# RocketFlightComputer.net
KiCad netlist of a schematic drawn in EAGLE
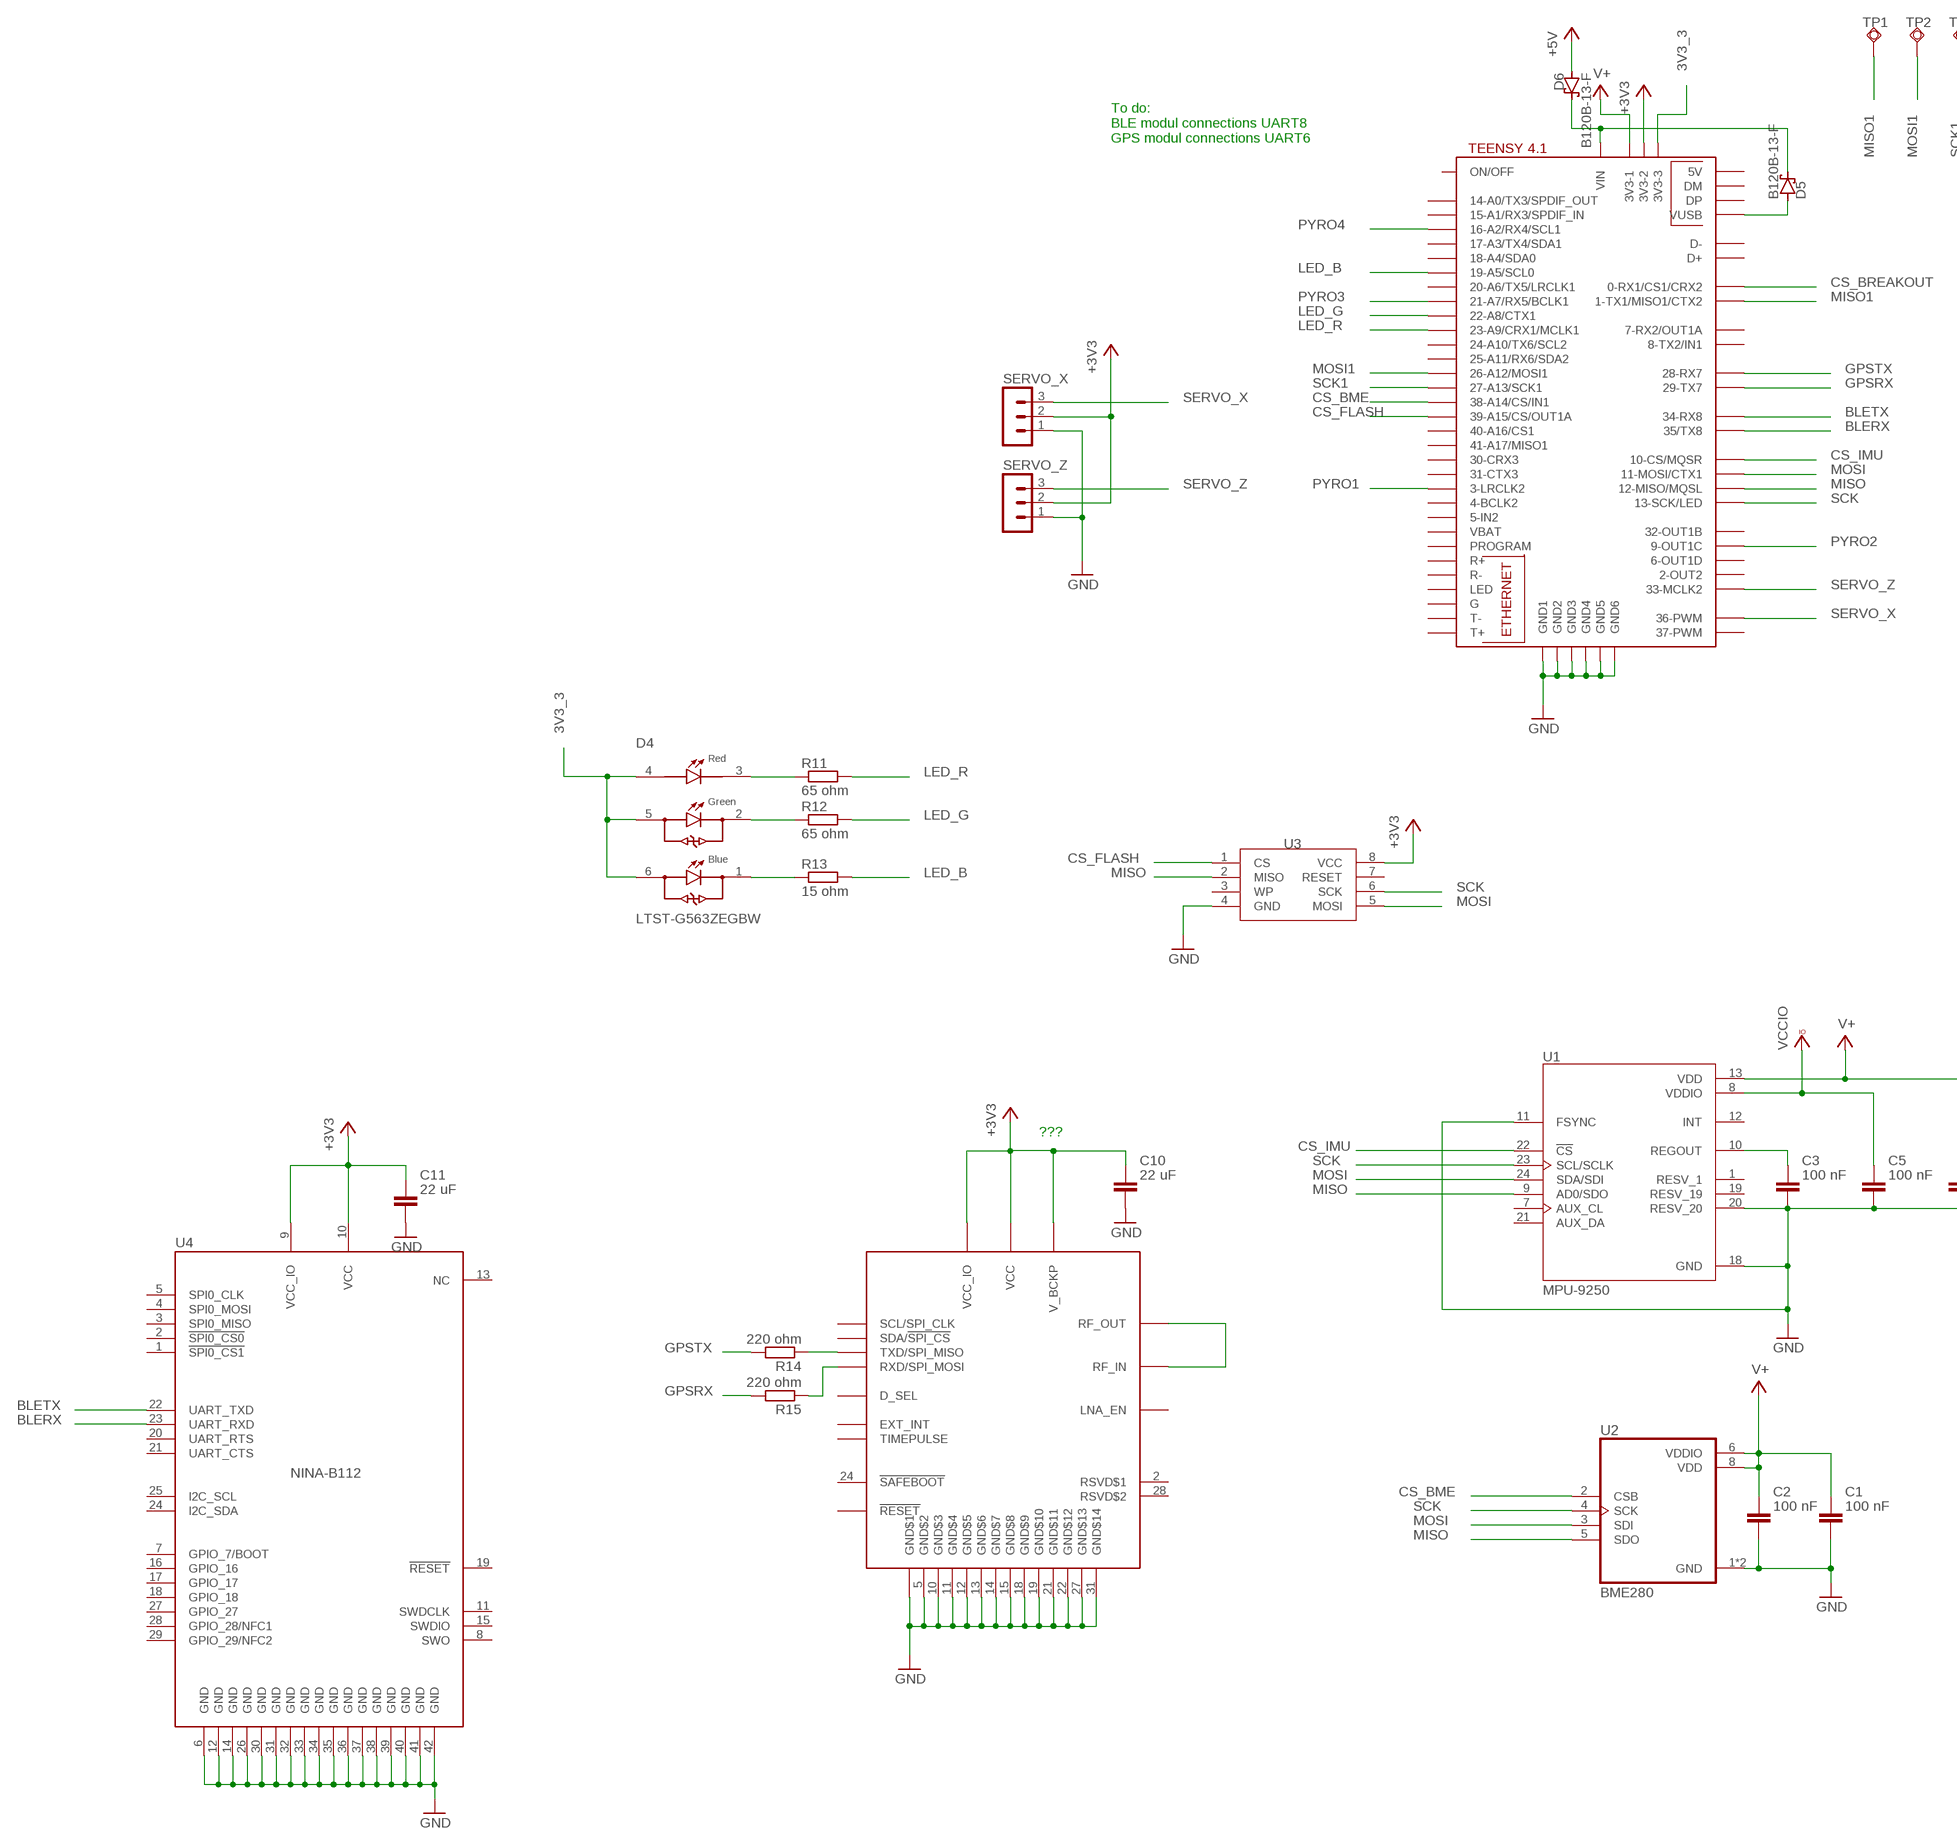
[diagram p0: schematic, sheet 1, part 1 of 2]
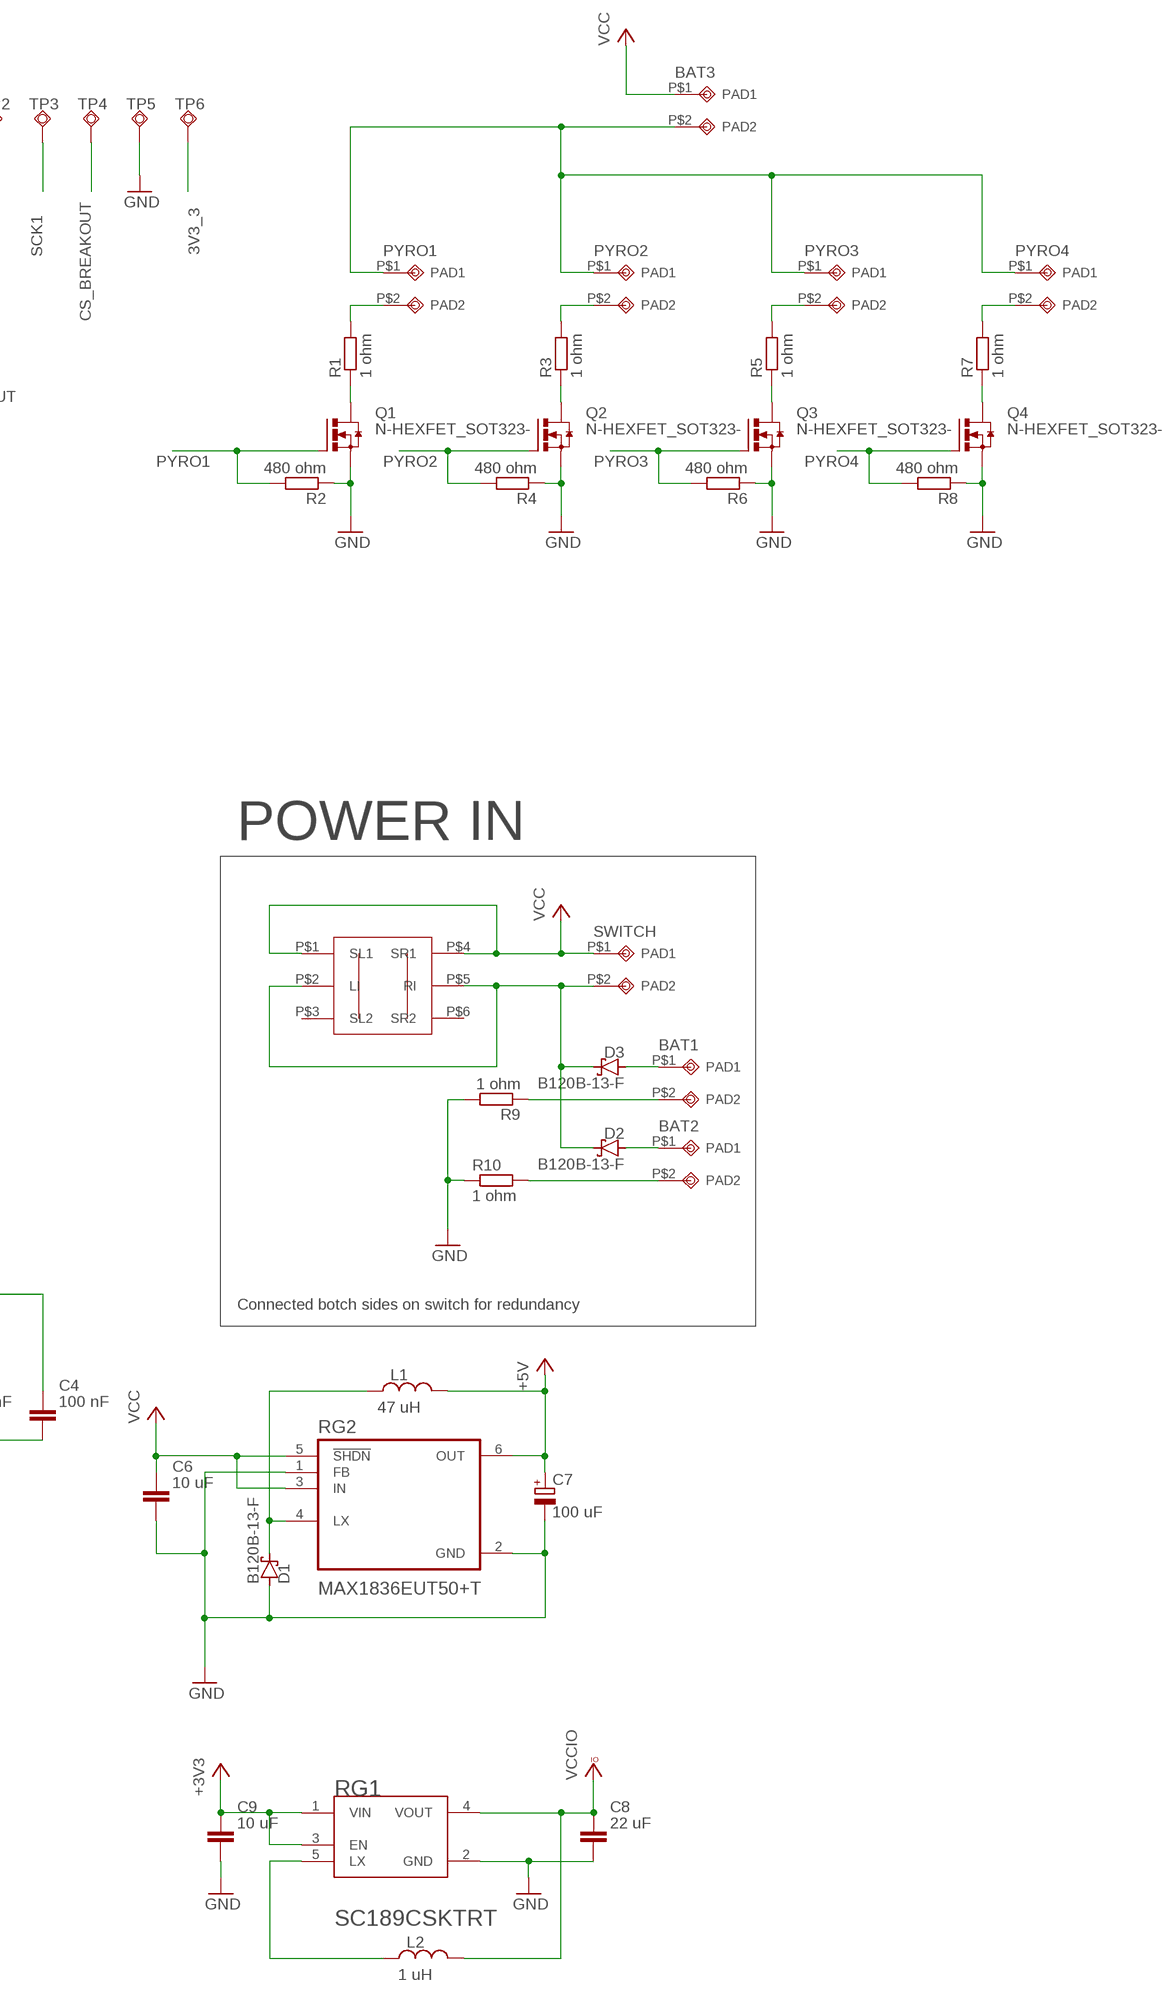
[diagram p1: schematic, sheet 1, part 2 of 2]

(export (version "E")
  (design (tool "Eeschema 10.0.6"))
  (components
    (comp (ref "BAT1")
      (value "2PINPAD")
      (footprint "eagle-import:2PINPAD")
      (libsource (lib "eagle-import") (part "2PINPAD"))
    )
    (comp (ref "BAT2")
      (value "2PINPAD")
      (footprint "eagle-import:2PINPAD")
      (libsource (lib "eagle-import") (part "2PINPAD"))
    )
    (comp (ref "BAT3")
      (value "2PINPAD")
      (footprint "eagle-import:2PINPAD")
      (libsource (lib "eagle-import") (part "2PINPAD"))
    )
    (comp (ref "C1")
      (value "100 nF")
      (footprint "eagle-import:CAPC3216X135")
      (libsource (lib "eagle-import") (part "CCHIP-1206(3216-METRIC)_"))
    )
    (comp (ref "C2")
      (value "100 nF")
      (footprint "eagle-import:CAPC3216X135")
      (libsource (lib "eagle-import") (part "CCHIP-1206(3216-METRIC)_"))
    )
    (comp (ref "C3")
      (value "100 nF")
      (footprint "eagle-import:CAPC3216X135")
      (libsource (lib "eagle-import") (part "CCHIP-1206(3216-METRIC)_"))
    )
    (comp (ref "C4")
      (value "100 nF")
      (footprint "eagle-import:CAPC3216X135")
      (libsource (lib "eagle-import") (part "CCHIP-1206(3216-METRIC)_"))
    )
    (comp (ref "C5")
      (value "100 nF")
      (footprint "eagle-import:CAPC3216X135")
      (libsource (lib "eagle-import") (part "CCHIP-1206(3216-METRIC)_"))
    )
    (comp (ref "C6")
      (value "10 uF")
      (footprint "eagle-import:CAPC3216X135")
      (libsource (lib "eagle-import") (part "CCHIP-1206(3216-METRIC)_"))
    )
    (comp (ref "C7")
      (value "100 uF")
      (footprint "eagle-import:B_3528-21W")
      (libsource (lib "eagle-import") (part "CPOL-EUB/3528-21W"))
    )
    (comp (ref "C8")
      (value "22 uF")
      (footprint "eagle-import:CAPC3216X135")
      (libsource (lib "eagle-import") (part "CCHIP-1206(3216-METRIC)_"))
    )
    (comp (ref "C9")
      (value "10 uF")
      (footprint "eagle-import:CAPC3216X135")
      (libsource (lib "eagle-import") (part "CCHIP-1206(3216-METRIC)_"))
    )
    (comp (ref "C10")
      (value "22 uF")
      (footprint "eagle-import:CAPC3216X135")
      (libsource (lib "eagle-import") (part "CCHIP-1206(3216-METRIC)_"))
    )
    (comp (ref "C11")
      (value "22 uF")
      (footprint "eagle-import:CAPC3216X135")
      (libsource (lib "eagle-import") (part "CCHIP-1206(3216-METRIC)_"))
    )
    (comp (ref "D1")
      (value "B120B-13-F")
      (footprint "eagle-import:SMB")
      (libsource (lib "eagle-import") (part "B120B-13-F"))
    )
    (comp (ref "D2")
      (value "B120B-13-F")
      (footprint "eagle-import:SMB")
      (libsource (lib "eagle-import") (part "B120B-13-F"))
    )
    (comp (ref "D3")
      (value "B120B-13-F")
      (footprint "eagle-import:SMB")
      (libsource (lib "eagle-import") (part "B120B-13-F"))
    )
    (comp (ref "D4")
      (value "LTST-G563ZEGBW")
      (footprint "eagle-import:LED_LTST-G563ZEGBW")
      (fields (field (name "MF") "Lite-On"))
      (libsource (lib "eagle-import") (part "LTST-G563ZEGBW"))
    )
    (comp (ref "D5")
      (value "B120B-13-F")
      (footprint "eagle-import:SMB")
      (libsource (lib "eagle-import") (part "B120B-13-F"))
    )
    (comp (ref "D6")
      (value "B120B-13-F")
      (footprint "eagle-import:SMB")
      (libsource (lib "eagle-import") (part "B120B-13-F"))
    )
    (comp (ref "L1")
      (value "47 uH")
      (footprint "eagle-import:INDM3225X240")
      (libsource (lib "eagle-import") (part "LMOLDED-1210(3225-METRIC)_"))
    )
    (comp (ref "L2")
      (value "1 uH")
      (footprint "eagle-import:CAPC2012X110")
      (libsource (lib "eagle-import") (part "CW0805-10002012"))
    )
    (comp (ref "PYRO1")
      (value "2PINPAD")
      (footprint "eagle-import:2PINPAD")
      (libsource (lib "eagle-import") (part "2PINPAD"))
    )
    (comp (ref "PYRO2")
      (value "2PINPAD")
      (footprint "eagle-import:2PINPAD")
      (libsource (lib "eagle-import") (part "2PINPAD"))
    )
    (comp (ref "PYRO3")
      (value "2PINPAD")
      (footprint "eagle-import:2PINPAD")
      (libsource (lib "eagle-import") (part "2PINPAD"))
    )
    (comp (ref "PYRO4")
      (value "2PINPAD")
      (footprint "eagle-import:2PINPAD")
      (libsource (lib "eagle-import") (part "2PINPAD"))
    )
    (comp (ref "Q1")
      (value "N-HEXFET_SOT323-")
      (footprint "eagle-import:SOT223")
      (libsource (lib "eagle-import") (part "N-HEXFET_?-SOT323"))
    )
    (comp (ref "Q2")
      (value "N-HEXFET_SOT323-")
      (footprint "eagle-import:SOT223")
      (libsource (lib "eagle-import") (part "N-HEXFET_?-SOT323"))
    )
    (comp (ref "Q3")
      (value "N-HEXFET_SOT323-")
      (footprint "eagle-import:SOT223")
      (libsource (lib "eagle-import") (part "N-HEXFET_?-SOT323"))
    )
    (comp (ref "Q4")
      (value "N-HEXFET_SOT323-")
      (footprint "eagle-import:SOT223")
      (libsource (lib "eagle-import") (part "N-HEXFET_?-SOT323"))
    )
    (comp (ref "R1")
      (value "1 ohm")
      (footprint "eagle-import:R1206")
      (libsource (lib "eagle-import") (part "RR1206"))
    )
    (comp (ref "R2")
      (value "480 ohm")
      (footprint "eagle-import:R1206")
      (libsource (lib "eagle-import") (part "RR1206"))
    )
    (comp (ref "R3")
      (value "1 ohm")
      (footprint "eagle-import:R1206")
      (libsource (lib "eagle-import") (part "RR1206"))
    )
    (comp (ref "R4")
      (value "480 ohm")
      (footprint "eagle-import:R1206")
      (libsource (lib "eagle-import") (part "RR1206"))
    )
    (comp (ref "R5")
      (value "1 ohm")
      (footprint "eagle-import:R1206")
      (libsource (lib "eagle-import") (part "RR1206"))
    )
    (comp (ref "R6")
      (value "480 ohm")
      (footprint "eagle-import:R1206")
      (libsource (lib "eagle-import") (part "RR1206"))
    )
    (comp (ref "R7")
      (value "1 ohm")
      (footprint "eagle-import:R1206")
      (libsource (lib "eagle-import") (part "RR1206"))
    )
    (comp (ref "R8")
      (value "480 ohm")
      (footprint "eagle-import:R1206")
      (libsource (lib "eagle-import") (part "RR1206"))
    )
    (comp (ref "R9")
      (value "1 ohm")
      (footprint "eagle-import:R1206")
      (libsource (lib "eagle-import") (part "RR1206"))
    )
    (comp (ref "R10")
      (value "1 ohm")
      (footprint "eagle-import:R1206")
      (libsource (lib "eagle-import") (part "RR1206"))
    )
    (comp (ref "R11")
      (value "65 ohm")
      (footprint "eagle-import:R1206")
      (libsource (lib "eagle-import") (part "RR1206"))
    )
    (comp (ref "R12")
      (value "65 ohm")
      (footprint "eagle-import:R1206")
      (libsource (lib "eagle-import") (part "RR1206"))
    )
    (comp (ref "R13")
      (value "15 ohm")
      (footprint "eagle-import:R1206")
      (libsource (lib "eagle-import") (part "RR1206"))
    )
    (comp (ref "R14")
      (value "220 ohm")
      (footprint "eagle-import:R1206")
      (libsource (lib "eagle-import") (part "RR1206"))
    )
    (comp (ref "R15")
      (value "220 ohm")
      (footprint "eagle-import:R1206")
      (libsource (lib "eagle-import") (part "RR1206"))
    )
    (comp (ref "RG1")
      (value "SEMTECH_SC189CSKTRTSEMTECH_SC189CSKTRT_0_0")
      (footprint "eagle-import:SEMTECH_SC189CSKTRT_0")
      (fields
        (field (name "DIGIKEY_PART_NUMBER") "SC189CSKCT-ND")
        (field (name "MF") "Semtech")
        (field (name "MOUSER_PART_NUMBER") "947-SC189CSKTRT")
      )
      (libsource (lib "eagle-import") (part "SEMTECH_SC189CSKTRTSEMTECH_SC189CSKTRT_0_0"))
    )
    (comp (ref "RG2")
      (value "MAX1836EUT50+T")
      (footprint "eagle-import:SOT95P280X145-6N")
      (fields (field (name "MF") "Maxim Integrated"))
      (libsource (lib "eagle-import") (part "MAX1836EUT50+T"))
    )
    (comp (ref "SERVO_X")
      (value "MA03-1")
      (footprint "eagle-import:MA03-1")
      (libsource (lib "eagle-import") (part "MA03-1"))
    )
    (comp (ref "SERVO_Z")
      (value "MA03-1")
      (footprint "eagle-import:MA03-1")
      (libsource (lib "eagle-import") (part "MA03-1"))
    )
    (comp (ref "SWITCH")
      (value "2PINPAD")
      (footprint "eagle-import:2PINPAD")
      (libsource (lib "eagle-import") (part "2PINPAD"))
    )
    (comp (ref "TP1")
      (value "TPSQTP13SQ")
      (footprint "eagle-import:TP13SQ")
      (libsource (lib "eagle-import") (part "TPSQTP13SQ"))
    )
    (comp (ref "TP2")
      (value "TPSQTP13SQ")
      (footprint "eagle-import:TP13SQ")
      (libsource (lib "eagle-import") (part "TPSQTP13SQ"))
    )
    (comp (ref "TP3")
      (value "TPSQTP13SQ")
      (footprint "eagle-import:TP13SQ")
      (libsource (lib "eagle-import") (part "TPSQTP13SQ"))
    )
    (comp (ref "TP4")
      (value "TPSQTP13SQ")
      (footprint "eagle-import:TP13SQ")
      (libsource (lib "eagle-import") (part "TPSQTP13SQ"))
    )
    (comp (ref "TP5")
      (value "TPSQTP13SQ")
      (footprint "eagle-import:TP13SQ")
      (libsource (lib "eagle-import") (part "TPSQTP13SQ"))
    )
    (comp (ref "TP6")
      (value "TPSQTP13SQ")
      (footprint "eagle-import:TP13SQ")
      (libsource (lib "eagle-import") (part "TPSQTP13SQ"))
    )
    (comp (ref "U$1")
      (value "TEENSY41")
      (footprint "eagle-import:TEENSY41")
      (libsource (lib "eagle-import") (part "TEENSY41"))
    )
    (comp (ref "U$2")
      (value "CAM-M8")
      (footprint "eagle-import:CAM-M8")
      (libsource (lib "eagle-import") (part "CAM-M8"))
    )
    (comp (ref "U$3")
      (value "DUAL_SW")
      (footprint "eagle-import:DUAL_SWITCH")
      (libsource (lib "eagle-import") (part "DUAL_SW"))
    )
    (comp (ref "U1")
      (value "MPU-9250")
      (footprint "eagle-import:QFN40P300X300X105-24N")
      (fields (field (name "MF") "TDK InvenSense"))
      (libsource (lib "eagle-import") (part "MPU-9250"))
    )
    (comp (ref "U2")
      (value "BME280")
      (footprint "eagle-import:PSON65P250X250X100-8N")
      (fields (field (name "MF") "Bosch"))
      (libsource (lib "eagle-import") (part "BME280"))
    )
    (comp (ref "U3")
      (value "FLASHSOIC8")
      (footprint "eagle-import:SOIC127P600X175-8N")
      (libsource (lib "eagle-import") (part "FLASHSOIC8"))
    )
    (comp (ref "U4")
      (value "NINA-B112")
      (footprint "eagle-import:NINA112-42")
      (libsource (lib "eagle-import") (part "NINA-B112"))
    )
  )
  (nets
    (net (code "1") (name "+3V3") (class "Default")
      (node (ref "C10") (pin "1") (pinfunction "1_1") (pintype "passive"))
      (node (ref "C11") (pin "1") (pinfunction "1_1") (pintype "passive"))
      (node (ref "C9") (pin "1") (pinfunction "1_1") (pintype "passive"))
      (node (ref "RG1") (pin "1") (pinfunction "VIN_1") (pintype "bidirectional"))
      (node (ref "RG1") (pin "3") (pinfunction "EN_3") (pintype "bidirectional"))
      (node (ref "SERVO_X") (pin "2") (pinfunction "2_2") (pintype "passive"))
      (node (ref "SERVO_Z") (pin "2") (pinfunction "2_2") (pintype "passive"))
      (node (ref "U$1") (pin "3V3-2") (pinfunction "3V3-2_3V3-2") (pintype "bidirectional"))
      (node (ref "U$2") (pin "1") (pinfunction "VCC_IO_1") (pintype "power_in"))
      (node (ref "U$2") (pin "8") (pinfunction "V_BCKP_8") (pintype "power_in"))
      (node (ref "U$2") (pin "9") (pinfunction "VCC_9") (pintype "power_in"))
      (node (ref "U3") (pin "8") (pinfunction "VCC_8") (pintype "bidirectional"))
      (node (ref "U4") (pin "10") (pinfunction "VCC_10") (pintype "power_in"))
      (node (ref "U4") (pin "9") (pinfunction "VCC_IO_9") (pintype "power_in"))
    )
    (net (code "2") (name "+5V") (class "Default")
      (node (ref "C7") (pin "+") (pinfunction "+_+") (pintype "passive"))
      (node (ref "D6") (pin "P$2") (pinfunction "A_P$2") (pintype "passive"))
      (node (ref "L1") (pin "2") (pinfunction "2_2") (pintype "passive"))
      (node (ref "RG2") (pin "6") (pinfunction "OUT_6") (pintype "output"))
    )
    (net (code "3") (name "/3V3_3") (class "Default")
      (node (ref "D4") (pin "4") (pinfunction "4_4") (pintype "passive"))
      (node (ref "D4") (pin "5") (pinfunction "5_5") (pintype "passive"))
      (node (ref "D4") (pin "6") (pinfunction "6_6") (pintype "passive"))
      (node (ref "TP6") (pin "TP") (pinfunction "TP_TP") (pintype "input"))
      (node (ref "U$1") (pin "3V3-3") (pinfunction "3V3-3_3V3-3") (pintype "bidirectional"))
    )
    (net (code "4") (name "/BLERX") (class "Default")
      (node (ref "U$1") (pin "35-TX8") (pinfunction "35/TX8_35-TX8") (pintype "bidirectional"))
      (node (ref "U4") (pin "23") (pinfunction "UART_RXD_23") (pintype "bidirectional"))
    )
    (net (code "5") (name "/BLETX") (class "Default")
      (node (ref "U$1") (pin "34-RX8") (pinfunction "34-RX8_34-RX8") (pintype "bidirectional"))
      (node (ref "U4") (pin "22") (pinfunction "UART_TXD_22") (pintype "bidirectional"))
    )
    (net (code "6") (name "/CS_BME") (class "Default")
      (node (ref "U$1") (pin "38-A14/CS/IN1") (pinfunction "38-A14/CS/IN1_38-A14/CS/IN1") (pintype "bidirectional"))
      (node (ref "U2") (pin "2") (pinfunction "CSB_2") (pintype "input"))
    )
    (net (code "7") (name "/CS_BREAKOUT") (class "Default")
      (node (ref "TP4") (pin "TP") (pinfunction "TP_TP") (pintype "input"))
      (node (ref "U$1") (pin "0-RX1/CS1/CRX2") (pinfunction "0-RX1/CS1/CRX2_0-RX1/CS1/CRX2") (pintype "bidirectional"))
    )
    (net (code "8") (name "/CS_FLASH") (class "Default")
      (node (ref "U$1") (pin "39-A15/CS/OUT1A") (pinfunction "39-A15/CS/OUT1A_39-A15/CS/OUT1A") (pintype "bidirectional"))
      (node (ref "U3") (pin "1") (pinfunction "CS_1") (pintype "bidirectional"))
    )
    (net (code "9") (name "/CS_IMU") (class "Default")
      (node (ref "U$1") (pin "10-CS\\MQSR") (pinfunction "10-CS/MQSR_10-CS\\MQSR") (pintype "bidirectional"))
      (node (ref "U1") (pin "22") (pinfunction "~{CS}_22") (pintype "input"))
    )
    (net (code "10") (name "/GPSRX") (class "Default")
      (node (ref "R15") (pin "2") (pinfunction "2_2") (pintype "passive"))
      (node (ref "U$1") (pin "29-TX7") (pinfunction "29-TX7_29-TX7") (pintype "bidirectional"))
    )
    (net (code "11") (name "/GPSTX") (class "Default")
      (node (ref "R14") (pin "2") (pinfunction "2_2") (pintype "passive"))
      (node (ref "U$1") (pin "28-RX7") (pinfunction "28-RX7_28-RX7") (pintype "bidirectional"))
    )
    (net (code "12") (name "/LED_B") (class "Default")
      (node (ref "R13") (pin "2") (pinfunction "2_2") (pintype "passive"))
      (node (ref "U$1") (pin "19-A5/SCL0") (pinfunction "19-A5/SCL0_19-A5/SCL0") (pintype "bidirectional"))
    )
    (net (code "13") (name "/LED_G") (class "Default")
      (node (ref "R12") (pin "2") (pinfunction "2_2") (pintype "passive"))
      (node (ref "U$1") (pin "22-A8/CTX1") (pinfunction "22-A8/CTX1_22-A8/CTX1") (pintype "bidirectional"))
    )
    (net (code "14") (name "/LED_R") (class "Default")
      (node (ref "R11") (pin "2") (pinfunction "2_2") (pintype "passive"))
      (node (ref "U$1") (pin "23-A9/CRX1/MCLK1") (pinfunction "23-A9/CRX1/MCLK1_23-A9/CRX1/MCLK1") (pintype "bidirectional"))
    )
    (net (code "15") (name "/MISO") (class "Default")
      (node (ref "U$1") (pin "12-MISO/MQSL") (pinfunction "12-MISO/MQSL_12-MISO/MQSL") (pintype "bidirectional"))
      (node (ref "U1") (pin "9") (pinfunction "AD0/SDO_9") (pintype "output"))
      (node (ref "U2") (pin "5") (pinfunction "SDO_5") (pintype "bidirectional"))
      (node (ref "U3") (pin "2") (pinfunction "MISO_2") (pintype "bidirectional"))
    )
    (net (code "16") (name "/MISO1") (class "Default")
      (node (ref "TP1") (pin "TP") (pinfunction "TP_TP") (pintype "input"))
      (node (ref "U$1") (pin "1-TX1/MISO1/CTX2") (pinfunction "1-TX1/MISO1/CTX2_1-TX1/MISO1/CTX2") (pintype "bidirectional"))
    )
    (net (code "17") (name "/MOSI") (class "Default")
      (node (ref "U$1") (pin "11-MOSI/CTX1") (pinfunction "11-MOSI/CTX1_11-MOSI/CTX1") (pintype "bidirectional"))
      (node (ref "U1") (pin "24") (pinfunction "SDA/SDI_24") (pintype "bidirectional"))
      (node (ref "U2") (pin "3") (pinfunction "SDI_3") (pintype "bidirectional"))
      (node (ref "U3") (pin "5") (pinfunction "MOSI_5") (pintype "bidirectional"))
    )
    (net (code "18") (name "/MOSI1") (class "Default")
      (node (ref "TP2") (pin "TP") (pinfunction "TP_TP") (pintype "input"))
      (node (ref "U$1") (pin "26-A12/MOSI1") (pinfunction "26-A12/MOSI1_26-A12/MOSI1") (pintype "bidirectional"))
    )
    (net (code "19") (name "/PYRO1") (class "Default")
      (node (ref "Q1") (pin "1") (pinfunction "G_1") (pintype "passive"))
      (node (ref "R2") (pin "2") (pinfunction "2_2") (pintype "passive"))
      (node (ref "U$1") (pin "3-LRCLK2") (pinfunction "3-LRCLK2_3-LRCLK2") (pintype "bidirectional"))
    )
    (net (code "20") (name "/PYRO2") (class "Default")
      (node (ref "Q2") (pin "1") (pinfunction "G_1") (pintype "passive"))
      (node (ref "R4") (pin "2") (pinfunction "2_2") (pintype "passive"))
      (node (ref "U$1") (pin "9-OUT1C") (pinfunction "9-OUT1C_9-OUT1C") (pintype "bidirectional"))
    )
    (net (code "21") (name "/PYRO3") (class "Default")
      (node (ref "Q3") (pin "1") (pinfunction "G_1") (pintype "passive"))
      (node (ref "R6") (pin "2") (pinfunction "2_2") (pintype "passive"))
      (node (ref "U$1") (pin "21-A7/RX5/BCLK1") (pinfunction "21-A7/RX5/BCLK1_21-A7/RX5/BCLK1") (pintype "bidirectional"))
    )
    (net (code "22") (name "/PYRO4") (class "Default")
      (node (ref "Q4") (pin "1") (pinfunction "G_1") (pintype "passive"))
      (node (ref "R8") (pin "2") (pinfunction "2_2") (pintype "passive"))
      (node (ref "U$1") (pin "16-A2/RX4/SCL1") (pinfunction "16-A2/RX4/SCL1_16-A2/RX4/SCL1") (pintype "bidirectional"))
    )
    (net (code "23") (name "/SCK") (class "Default")
      (node (ref "U$1") (pin "13-SCK/LED") (pinfunction "13-SCK/LED_13-SCK/LED") (pintype "bidirectional"))
      (node (ref "U1") (pin "23") (pinfunction "SCL/SCLK_23") (pintype "input"))
      (node (ref "U2") (pin "4") (pinfunction "SCK_4") (pintype "input"))
      (node (ref "U3") (pin "6") (pinfunction "SCK_6") (pintype "bidirectional"))
    )
    (net (code "24") (name "/SCK1") (class "Default")
      (node (ref "TP3") (pin "TP") (pinfunction "TP_TP") (pintype "input"))
      (node (ref "U$1") (pin "27-A13/SCK1") (pinfunction "27-A13/SCK1_27-A13/SCK1") (pintype "bidirectional"))
    )
    (net (code "25") (name "/SERVO_X") (class "Default")
      (node (ref "SERVO_X") (pin "3") (pinfunction "3_3") (pintype "passive"))
      (node (ref "U$1") (pin "36-PWM") (pinfunction "36-PWM_36-PWM") (pintype "bidirectional"))
    )
    (net (code "26") (name "/SERVO_Z") (class "Default")
      (node (ref "SERVO_Z") (pin "3") (pinfunction "3_3") (pintype "passive"))
      (node (ref "U$1") (pin "33-MCLK2") (pinfunction "33-MCLK2_33-MCLK2") (pintype "bidirectional"))
    )
    (net (code "27") (name "GND") (class "Default")
      (node (ref "C1") (pin "2") (pinfunction "2_2") (pintype "passive"))
      (node (ref "C10") (pin "2") (pinfunction "2_2") (pintype "passive"))
      (node (ref "C11") (pin "2") (pinfunction "2_2") (pintype "passive"))
      (node (ref "C2") (pin "2") (pinfunction "2_2") (pintype "passive"))
      (node (ref "C3") (pin "2") (pinfunction "2_2") (pintype "passive"))
      (node (ref "C4") (pin "2") (pinfunction "2_2") (pintype "passive"))
      (node (ref "C5") (pin "2") (pinfunction "2_2") (pintype "passive"))
      (node (ref "C6") (pin "2") (pinfunction "2_2") (pintype "passive"))
      (node (ref "C7") (pin "-") (pinfunction "-_-") (pintype "passive"))
      (node (ref "C8") (pin "2") (pinfunction "2_2") (pintype "passive"))
      (node (ref "C9") (pin "2") (pinfunction "2_2") (pintype "passive"))
      (node (ref "D1") (pin "P$2") (pinfunction "A_P$2") (pintype "passive"))
      (node (ref "Q1") (pin "3") (pinfunction "S_3") (pintype "passive"))
      (node (ref "Q2") (pin "3") (pinfunction "S_3") (pintype "passive"))
      (node (ref "Q3") (pin "3") (pinfunction "S_3") (pintype "passive"))
      (node (ref "Q4") (pin "3") (pinfunction "S_3") (pintype "passive"))
      (node (ref "R10") (pin "1") (pinfunction "1_1") (pintype "passive"))
      (node (ref "R2") (pin "1") (pinfunction "1_1") (pintype "passive"))
      (node (ref "R4") (pin "1") (pinfunction "1_1") (pintype "passive"))
      (node (ref "R6") (pin "1") (pinfunction "1_1") (pintype "passive"))
      (node (ref "R8") (pin "1") (pinfunction "1_1") (pintype "passive"))
      (node (ref "R9") (pin "2") (pinfunction "2_2") (pintype "passive"))
      (node (ref "RG1") (pin "2") (pinfunction "GND_2") (pintype "bidirectional"))
      (node (ref "RG2") (pin "1") (pinfunction "FB_1") (pintype "input"))
      (node (ref "RG2") (pin "2") (pinfunction "GND_2") (pintype "power_in"))
      (node (ref "SERVO_X") (pin "1") (pinfunction "1_1") (pintype "passive"))
      (node (ref "SERVO_Z") (pin "1") (pinfunction "1_1") (pintype "passive"))
      (node (ref "TP5") (pin "TP") (pinfunction "TP_TP") (pintype "input"))
      (node (ref "U$1") (pin "GND1") (pinfunction "GND1_GND1") (pintype "bidirectional"))
      (node (ref "U$1") (pin "GND2") (pinfunction "GND2_GND2") (pintype "bidirectional"))
      (node (ref "U$1") (pin "GND3") (pinfunction "GND3_GND3") (pintype "bidirectional"))
      (node (ref "U$1") (pin "GND4") (pinfunction "GND4_GND4") (pintype "bidirectional"))
      (node (ref "U$1") (pin "GND5") (pinfunction "GND5_GND5") (pintype "bidirectional"))
      (node (ref "U$1") (pin "GND6") (pinfunction "GND6_GND6") (pintype "bidirectional"))
      (node (ref "U$2") (pin "10") (pinfunction "GND$3_10") (pintype "power_in"))
      (node (ref "U$2") (pin "11") (pinfunction "GND$4_11") (pintype "power_in"))
      (node (ref "U$2") (pin "12") (pinfunction "GND$5_12") (pintype "power_in"))
      (node (ref "U$2") (pin "13") (pinfunction "GND$6_13") (pintype "power_in"))
      (node (ref "U$2") (pin "14") (pinfunction "GND$7_14") (pintype "power_in"))
      (node (ref "U$2") (pin "15") (pinfunction "GND$8_15") (pintype "power_in"))
      (node (ref "U$2") (pin "18") (pinfunction "GND$9_18") (pintype "power_in"))
      (node (ref "U$2") (pin "19") (pinfunction "GND$10_19") (pintype "power_in"))
      (node (ref "U$2") (pin "21") (pinfunction "GND$11_21") (pintype "power_in"))
      (node (ref "U$2") (pin "22") (pinfunction "GND$12_22") (pintype "power_in"))
      (node (ref "U$2") (pin "27") (pinfunction "GND$13_27") (pintype "power_in"))
      (node (ref "U$2") (pin "31") (pinfunction "GND$14_31") (pintype "power_in"))
      (node (ref "U$2") (pin "4") (pinfunction "GND$1_4") (pintype "power_in"))
      (node (ref "U$2") (pin "5") (pinfunction "GND$2_5") (pintype "power_in"))
      (node (ref "U1") (pin "11") (pinfunction "FSYNC_11") (pintype "input"))
      (node (ref "U1") (pin "18") (pinfunction "GND_18") (pintype "power_in"))
      (node (ref "U1") (pin "20") (pinfunction "RESV_20_20") (pintype "passive"))
      (node (ref "U2") (pin "1") (pinfunction "GND_1") (pintype "power_in"))
      (node (ref "U2") (pin "7") (pinfunction "GND_7") (pintype "power_in"))
      (node (ref "U3") (pin "4") (pinfunction "GND_4") (pintype "bidirectional"))
      (node (ref "U4") (pin "12") (pinfunction "GND_12") (pintype "power_in"))
      (node (ref "U4") (pin "14") (pinfunction "GND_14") (pintype "power_in"))
      (node (ref "U4") (pin "26") (pinfunction "GND_26") (pintype "power_in"))
      (node (ref "U4") (pin "30") (pinfunction "GND_30") (pintype "power_in"))
      (node (ref "U4") (pin "31") (pinfunction "GND_31") (pintype "power_in"))
      (node (ref "U4") (pin "32") (pinfunction "GND_32") (pintype "power_in"))
      (node (ref "U4") (pin "33") (pinfunction "GND_33") (pintype "power_in"))
      (node (ref "U4") (pin "34") (pinfunction "GND_34") (pintype "power_in"))
      (node (ref "U4") (pin "35") (pinfunction "GND_35") (pintype "power_in"))
      (node (ref "U4") (pin "36") (pinfunction "GND_36") (pintype "power_in"))
      (node (ref "U4") (pin "37") (pinfunction "GND_37") (pintype "power_in"))
      (node (ref "U4") (pin "38") (pinfunction "GND_38") (pintype "power_in"))
      (node (ref "U4") (pin "39") (pinfunction "GND_39") (pintype "power_in"))
      (node (ref "U4") (pin "40") (pinfunction "GND_40") (pintype "power_in"))
      (node (ref "U4") (pin "41") (pinfunction "GND_41") (pintype "power_in"))
      (node (ref "U4") (pin "42") (pinfunction "GND_42") (pintype "power_in"))
      (node (ref "U4") (pin "6") (pinfunction "GND_6") (pintype "power_in"))
    )
    (net (code "28") (name "Net-(BAT1-PAD1)") (class "Default")
      (node (ref "BAT1") (pin "P$1") (pinfunction "PAD1_P$1") (pintype "bidirectional"))
      (node (ref "D3") (pin "P$2") (pinfunction "A_P$2") (pintype "passive"))
    )
    (net (code "29") (name "Net-(BAT1-PAD2)") (class "Default")
      (node (ref "BAT1") (pin "P$2") (pinfunction "PAD2_P$2") (pintype "bidirectional"))
      (node (ref "R9") (pin "1") (pinfunction "1_1") (pintype "passive"))
    )
    (net (code "30") (name "Net-(BAT2-PAD1)") (class "Default")
      (node (ref "BAT2") (pin "P$1") (pinfunction "PAD1_P$1") (pintype "bidirectional"))
      (node (ref "D2") (pin "P$2") (pinfunction "A_P$2") (pintype "passive"))
    )
    (net (code "31") (name "Net-(BAT2-PAD2)") (class "Default")
      (node (ref "BAT2") (pin "P$2") (pinfunction "PAD2_P$2") (pintype "bidirectional"))
      (node (ref "R10") (pin "2") (pinfunction "2_2") (pintype "passive"))
    )
    (net (code "32") (name "Net-(BAT3-PAD2)") (class "Default")
      (node (ref "BAT3") (pin "P$2") (pinfunction "PAD2_P$2") (pintype "bidirectional"))
      (node (ref "PYRO1") (pin "P$1") (pinfunction "PAD1_P$1") (pintype "bidirectional"))
      (node (ref "PYRO2") (pin "P$1") (pinfunction "PAD1_P$1") (pintype "bidirectional"))
      (node (ref "PYRO3") (pin "P$1") (pinfunction "PAD1_P$1") (pintype "bidirectional"))
      (node (ref "PYRO4") (pin "P$1") (pinfunction "PAD1_P$1") (pintype "bidirectional"))
    )
    (net (code "33") (name "Net-(D1-B)") (class "Default")
      (node (ref "D1") (pin "P$1") (pinfunction "B_P$1") (pintype "passive"))
      (node (ref "L1") (pin "1") (pinfunction "1_1") (pintype "passive"))
      (node (ref "RG2") (pin "4") (pinfunction "LX_4") (pintype "bidirectional"))
    )
    (net (code "34") (name "Net-(D2-B)") (class "Default")
      (node (ref "D2") (pin "P$1") (pinfunction "B_P$1") (pintype "passive"))
      (node (ref "D3") (pin "P$1") (pinfunction "B_P$1") (pintype "passive"))
      (node (ref "SWITCH") (pin "P$2") (pinfunction "PAD2_P$2") (pintype "bidirectional"))
      (node (ref "U$3") (pin "P$2") (pinfunction "LI_P$2") (pintype "bidirectional"))
      (node (ref "U$3") (pin "P$5") (pinfunction "RI_P$5") (pintype "bidirectional"))
    )
    (net (code "35") (name "Net-(D4-Pad1)") (class "Default")
      (node (ref "D4") (pin "1") (pinfunction "1_1") (pintype "passive"))
      (node (ref "R13") (pin "1") (pinfunction "1_1") (pintype "passive"))
    )
    (net (code "36") (name "Net-(D4-Pad2)") (class "Default")
      (node (ref "D4") (pin "2") (pinfunction "2_2") (pintype "passive"))
      (node (ref "R12") (pin "1") (pinfunction "1_1") (pintype "passive"))
    )
    (net (code "37") (name "Net-(D4-Pad3)") (class "Default")
      (node (ref "D4") (pin "3") (pinfunction "3_3") (pintype "passive"))
      (node (ref "R11") (pin "1") (pinfunction "1_1") (pintype "passive"))
    )
    (net (code "38") (name "Net-(D5-A)") (class "Default")
      (node (ref "D5") (pin "P$2") (pinfunction "A_P$2") (pintype "passive"))
      (node (ref "U$1") (pin "VUSB") (pinfunction "VUSB_VUSB") (pintype "bidirectional"))
    )
    (net (code "39") (name "Net-(D5-B)") (class "Default")
      (node (ref "D5") (pin "P$1") (pinfunction "B_P$1") (pintype "passive"))
      (node (ref "D6") (pin "P$1") (pinfunction "B_P$1") (pintype "passive"))
      (node (ref "U$1") (pin "VIN") (pinfunction "VIN_VIN") (pintype "bidirectional"))
    )
    (net (code "40") (name "Net-(PYRO1-PAD2)") (class "Default")
      (node (ref "PYRO1") (pin "P$2") (pinfunction "PAD2_P$2") (pintype "bidirectional"))
      (node (ref "R1") (pin "2") (pinfunction "2_2") (pintype "passive"))
    )
    (net (code "41") (name "Net-(PYRO2-PAD2)") (class "Default")
      (node (ref "PYRO2") (pin "P$2") (pinfunction "PAD2_P$2") (pintype "bidirectional"))
      (node (ref "R3") (pin "2") (pinfunction "2_2") (pintype "passive"))
    )
    (net (code "42") (name "Net-(PYRO3-PAD2)") (class "Default")
      (node (ref "PYRO3") (pin "P$2") (pinfunction "PAD2_P$2") (pintype "bidirectional"))
      (node (ref "R5") (pin "2") (pinfunction "2_2") (pintype "passive"))
    )
    (net (code "43") (name "Net-(PYRO4-PAD2)") (class "Default")
      (node (ref "PYRO4") (pin "P$2") (pinfunction "PAD2_P$2") (pintype "bidirectional"))
      (node (ref "R7") (pin "2") (pinfunction "2_2") (pintype "passive"))
    )
    (net (code "44") (name "Net-(Q1-D)") (class "Default")
      (node (ref "Q1") (pin "4") (pinfunction "D_4") (pintype "passive"))
      (node (ref "R1") (pin "1") (pinfunction "1_1") (pintype "passive"))
    )
    (net (code "45") (name "Net-(Q2-D)") (class "Default")
      (node (ref "Q2") (pin "4") (pinfunction "D_4") (pintype "passive"))
      (node (ref "R3") (pin "1") (pinfunction "1_1") (pintype "passive"))
    )
    (net (code "46") (name "Net-(Q3-D)") (class "Default")
      (node (ref "Q3") (pin "4") (pinfunction "D_4") (pintype "passive"))
      (node (ref "R5") (pin "1") (pinfunction "1_1") (pintype "passive"))
    )
    (net (code "47") (name "Net-(Q4-D)") (class "Default")
      (node (ref "Q4") (pin "4") (pinfunction "D_4") (pintype "passive"))
      (node (ref "R7") (pin "1") (pinfunction "1_1") (pintype "passive"))
    )
    (net (code "48") (name "Net-(RG1-LX)") (class "Default")
      (node (ref "L2") (pin "1") (pinfunction "1_1") (pintype "passive"))
      (node (ref "RG1") (pin "5") (pinfunction "LX_5") (pintype "bidirectional"))
    )
    (net (code "49") (name "Net-(U$2-RF_IN)") (class "Default")
      (node (ref "U$2") (pin "16") (pinfunction "RF_OUT_16") (pintype "output"))
      (node (ref "U$2") (pin "17") (pinfunction "RF_IN_17") (pintype "input"))
    )
    (net (code "50") (name "Net-(U$2-RXD{slash}SPI_MOSI)") (class "Default")
      (node (ref "R15") (pin "1") (pinfunction "1_1") (pintype "passive"))
      (node (ref "U$2") (pin "26") (pinfunction "RXD/SPI_MOSI_26") (pintype "input"))
    )
    (net (code "51") (name "Net-(U$2-TXD{slash}SPI_MISO)") (class "Default")
      (node (ref "R14") (pin "1") (pinfunction "1_1") (pintype "passive"))
      (node (ref "U$2") (pin "25") (pinfunction "TXD/SPI_MISO_25") (pintype "output"))
    )
    (net (code "52") (name "Net-(U1-REGOUT)") (class "Default")
      (node (ref "C3") (pin "1") (pinfunction "1_1") (pintype "passive"))
      (node (ref "U1") (pin "10") (pinfunction "REGOUT_10") (pintype "output"))
    )
    (net (code "53") (name "V+") (class "Default")
      (node (ref "C1") (pin "1") (pinfunction "1_1") (pintype "passive"))
      (node (ref "C2") (pin "1") (pinfunction "1_1") (pintype "passive"))
      (node (ref "C4") (pin "1") (pinfunction "1_1") (pintype "passive"))
      (node (ref "U$1") (pin "3V3-1") (pinfunction "3V3-1_3V3-1") (pintype "bidirectional"))
      (node (ref "U1") (pin "13") (pinfunction "VDD_13") (pintype "power_in"))
      (node (ref "U2") (pin "6") (pinfunction "VDDIO_6") (pintype "power_in"))
      (node (ref "U2") (pin "8") (pinfunction "VDD_8") (pintype "power_in"))
    )
    (net (code "54") (name "VCC") (class "Default")
      (node (ref "BAT3") (pin "P$1") (pinfunction "PAD1_P$1") (pintype "bidirectional"))
      (node (ref "C6") (pin "1") (pinfunction "1_1") (pintype "passive"))
      (node (ref "RG2") (pin "3") (pinfunction "IN_3") (pintype "input"))
      (node (ref "RG2") (pin "5") (pinfunction "~{SHDN}_5") (pintype "input"))
      (node (ref "SWITCH") (pin "P$1") (pinfunction "PAD1_P$1") (pintype "bidirectional"))
      (node (ref "U$3") (pin "P$1") (pinfunction "SL1_P$1") (pintype "bidirectional"))
      (node (ref "U$3") (pin "P$4") (pinfunction "SR1_P$4") (pintype "bidirectional"))
    )
    (net (code "55") (name "VCCIO") (class "Default")
      (node (ref "C5") (pin "1") (pinfunction "1_1") (pintype "passive"))
      (node (ref "C8") (pin "1") (pinfunction "1_1") (pintype "passive"))
      (node (ref "L2") (pin "2") (pinfunction "2_2") (pintype "passive"))
      (node (ref "RG1") (pin "4") (pinfunction "VOUT_4") (pintype "bidirectional"))
      (node (ref "U1") (pin "8") (pinfunction "VDDIO_8") (pintype "power_in"))
    )
    (net (code "56") (name "unconnected-(U$1-5V-Pad+5V)") (class "Default")
      (node (ref "U$1") (pin "+5V") (pinfunction "5V_+5V") (pintype "bidirectional"))
    )
    (net (code "57") (name "unconnected-(U$1-Pad2-OUT2)") (class "Default")
      (node (ref "U$1") (pin "2-OUT2") (pinfunction "2-OUT2_2-OUT2") (pintype "bidirectional"))
    )
    (net (code "58") (name "unconnected-(U$1-Pad4-BCLK2)") (class "Default")
      (node (ref "U$1") (pin "4-BCLK2") (pinfunction "4-BCLK2_4-BCLK2") (pintype "bidirectional"))
    )
    (net (code "59") (name "unconnected-(U$1-Pad5-IN2)") (class "Default")
      (node (ref "U$1") (pin "5-IN2") (pinfunction "5-IN2_5-IN2") (pintype "bidirectional"))
    )
    (net (code "60") (name "unconnected-(U$1-Pad6-OUT1D)") (class "Default")
      (node (ref "U$1") (pin "6-OUT1D") (pinfunction "6-OUT1D_6-OUT1D") (pintype "bidirectional"))
    )
    (net (code "61") (name "unconnected-(U$1-Pad7-RX2{slash}OUT1A)") (class "Default")
      (node (ref "U$1") (pin "7-RX2/OUT1A") (pinfunction "7-RX2/OUT1A_7-RX2/OUT1A") (pintype "bidirectional"))
    )
    (net (code "62") (name "unconnected-(U$1-Pad8-TX2{slash}IN1)") (class "Default")
      (node (ref "U$1") (pin "8-TX2/IN1") (pinfunction "8-TX2/IN1_8-TX2/IN1") (pintype "bidirectional"))
    )
    (net (code "63") (name "unconnected-(U$1-Pad14-A0{slash}TX3{slash}SPDIF_OUT)") (class "Default")
      (node (ref "U$1") (pin "14-A0/TX3/SPDIF_OUT") (pinfunction "14-A0/TX3/SPDIF_OUT_14-A0/TX3/SPDIF_OUT") (pintype "bidirectional"))
    )
    (net (code "64") (name "unconnected-(U$1-Pad15-A1{slash}RX3{slash}SPDIF_IN)") (class "Default")
      (node (ref "U$1") (pin "15-A1/RX3/SPDIF_IN") (pinfunction "15-A1/RX3/SPDIF_IN_15-A1/RX3/SPDIF_IN") (pintype "bidirectional"))
    )
    (net (code "65") (name "unconnected-(U$1-Pad17-A3{slash}TX4{slash}SDA1)") (class "Default")
      (node (ref "U$1") (pin "17-A3/TX4/SDA1") (pinfunction "17-A3/TX4/SDA1_17-A3/TX4/SDA1") (pintype "bidirectional"))
    )
    (net (code "66") (name "unconnected-(U$1-Pad18-A4{slash}SDA0)") (class "Default")
      (node (ref "U$1") (pin "18-A4/SDA0") (pinfunction "18-A4/SDA0_18-A4/SDA0") (pintype "bidirectional"))
    )
    (net (code "67") (name "unconnected-(U$1-Pad20-A6{slash}TX5{slash}LRCLK1)") (class "Default")
      (node (ref "U$1") (pin "20-A6/TX5/LRCLK1") (pinfunction "20-A6/TX5/LRCLK1_20-A6/TX5/LRCLK1") (pintype "bidirectional"))
    )
    (net (code "68") (name "unconnected-(U$1-Pad24-A10{slash}TX6{slash}SCL2)") (class "Default")
      (node (ref "U$1") (pin "24-A10/TX6/SCL2") (pinfunction "24-A10/TX6/SCL2_24-A10/TX6/SCL2") (pintype "bidirectional"))
    )
    (net (code "69") (name "unconnected-(U$1-Pad25-A11{slash}RX6{slash}SDA2)") (class "Default")
      (node (ref "U$1") (pin "25-A11/RX6/SDA2") (pinfunction "25-A11/RX6/SDA2_25-A11/RX6/SDA2") (pintype "bidirectional"))
    )
    (net (code "70") (name "unconnected-(U$1-Pad30-CRX3)") (class "Default")
      (node (ref "U$1") (pin "30-CRX3") (pinfunction "30-CRX3_30-CRX3") (pintype "bidirectional"))
    )
    (net (code "71") (name "unconnected-(U$1-Pad31-CTX3)") (class "Default")
      (node (ref "U$1") (pin "31-CTX3") (pinfunction "31-CTX3_31-CTX3") (pintype "bidirectional"))
    )
    (net (code "72") (name "unconnected-(U$1-Pad32-OUT1B)") (class "Default")
      (node (ref "U$1") (pin "32-OUT1B") (pinfunction "32-OUT1B_32-OUT1B") (pintype "bidirectional"))
    )
    (net (code "73") (name "unconnected-(U$1-Pad37-PWM)") (class "Default")
      (node (ref "U$1") (pin "37-PWM") (pinfunction "37-PWM_37-PWM") (pintype "bidirectional"))
    )
    (net (code "74") (name "unconnected-(U$1-Pad40-A16{slash}CS1)") (class "Default")
      (node (ref "U$1") (pin "40-A16/CS1") (pinfunction "40-A16/CS1_40-A16/CS1") (pintype "bidirectional"))
    )
    (net (code "75") (name "unconnected-(U$1-Pad41-A17{slash}MISO1)") (class "Default")
      (node (ref "U$1") (pin "41-A17/MISO1") (pinfunction "41-A17/MISO1_41-A17/MISO1") (pintype "bidirectional"))
    )
    (net (code "76") (name "unconnected-(U$1-PadD+)") (class "Default")
      (node (ref "U$1") (pin "D+") (pinfunction "D+_D+") (pintype "bidirectional"))
    )
    (net (code "77") (name "unconnected-(U$1-PadD-)") (class "Default")
      (node (ref "U$1") (pin "D-") (pinfunction "D-_D-") (pintype "bidirectional"))
    )
    (net (code "78") (name "unconnected-(U$1-PadDM)") (class "Default")
      (node (ref "U$1") (pin "DM") (pinfunction "DM_DM") (pintype "bidirectional"))
    )
    (net (code "79") (name "unconnected-(U$1-PadDP)") (class "Default")
      (node (ref "U$1") (pin "DP") (pinfunction "DP_DP") (pintype "bidirectional"))
    )
    (net (code "80") (name "unconnected-(U$1-PadG)") (class "Default")
      (node (ref "U$1") (pin "G") (pinfunction "G_G") (pintype "bidirectional"))
    )
    (net (code "81") (name "unconnected-(U$1-PadLED)") (class "Default")
      (node (ref "U$1") (pin "LED") (pinfunction "LED_LED") (pintype "bidirectional"))
    )
    (net (code "82") (name "unconnected-(U$1-PadON{slash}OFF)") (class "Default")
      (node (ref "U$1") (pin "ON/OFF") (pinfunction "ON/OFF_ON/OFF") (pintype "bidirectional"))
    )
    (net (code "83") (name "unconnected-(U$1-PadPROGRAM)") (class "Default")
      (node (ref "U$1") (pin "PROGRAM") (pinfunction "PROGRAM_PROGRAM") (pintype "bidirectional"))
    )
    (net (code "84") (name "unconnected-(U$1-PadR+)") (class "Default")
      (node (ref "U$1") (pin "R+") (pinfunction "R+_R+") (pintype "bidirectional"))
    )
    (net (code "85") (name "unconnected-(U$1-PadR-)") (class "Default")
      (node (ref "U$1") (pin "R-") (pinfunction "R-_R-") (pintype "bidirectional"))
    )
    (net (code "86") (name "unconnected-(U$1-PadT+)") (class "Default")
      (node (ref "U$1") (pin "T+") (pinfunction "T+_T+") (pintype "bidirectional"))
    )
    (net (code "87") (name "unconnected-(U$1-PadT-)") (class "Default")
      (node (ref "U$1") (pin "T-") (pinfunction "T-_T-") (pintype "bidirectional"))
    )
    (net (code "88") (name "unconnected-(U$1-PadVBAT)") (class "Default")
      (node (ref "U$1") (pin "VBAT") (pinfunction "VBAT_VBAT") (pintype "bidirectional"))
    )
    (net (code "89") (name "unconnected-(U$2-D_SEL-Pad20)") (class "Default")
      (node (ref "U$2") (pin "20") (pinfunction "D_SEL_20") (pintype "input"))
    )
    (net (code "90") (name "unconnected-(U$2-EXT_INT-Pad7)") (class "Default")
      (node (ref "U$2") (pin "7") (pinfunction "EXT_INT_7") (pintype "bidirectional"))
    )
    (net (code "91") (name "unconnected-(U$2-LNA_EN-Pad30)") (class "Default")
      (node (ref "U$2") (pin "30") (pinfunction "LNA_EN_30") (pintype "output"))
    )
    (net (code "92") (name "unconnected-(U$2-RSVD$1-Pad2)") (class "Default")
      (node (ref "U$2") (pin "2") (pinfunction "RSVD$1_2") (pintype "no_connect"))
    )
    (net (code "93") (name "unconnected-(U$2-RSVD$2-Pad28)") (class "Default")
      (node (ref "U$2") (pin "28") (pinfunction "RSVD$2_28") (pintype "no_connect"))
    )
    (net (code "94") (name "unconnected-(U$2-SCL{slash}SPI_CLK-Pad6)") (class "Default")
      (node (ref "U$2") (pin "6") (pinfunction "SCL/SPI_CLK_6") (pintype "input"))
    )
    (net (code "95") (name "unconnected-(U$2-SDA{slash}~{SPI_CS}-Pad3)") (class "Default")
      (node (ref "U$2") (pin "3") (pinfunction "SDA/~{SPI_CS}_3") (pintype "bidirectional"))
    )
    (net (code "96") (name "unconnected-(U$2-TIMEPULSE-Pad29)") (class "Default")
      (node (ref "U$2") (pin "29") (pinfunction "TIMEPULSE_29") (pintype "output"))
    )
    (net (code "97") (name "unconnected-(U$2-~{RESET}-Pad23)") (class "Default")
      (node (ref "U$2") (pin "23") (pinfunction "~{RESET}_23") (pintype "input"))
    )
    (net (code "98") (name "unconnected-(U$2-~{SAFEBOOT}-Pad24)") (class "Default")
      (node (ref "U$2") (pin "24") (pinfunction "~{SAFEBOOT}_24") (pintype "input"))
    )
    (net (code "99") (name "unconnected-(U$3-SL2-PadP$3)") (class "Default")
      (node (ref "U$3") (pin "P$3") (pinfunction "SL2_P$3") (pintype "bidirectional"))
    )
    (net (code "100") (name "unconnected-(U$3-SR2-PadP$6)") (class "Default")
      (node (ref "U$3") (pin "P$6") (pinfunction "SR2_P$6") (pintype "bidirectional"))
    )
    (net (code "101") (name "unconnected-(U1-AUX_CL-Pad7)") (class "Default")
      (node (ref "U1") (pin "7") (pinfunction "AUX_CL_7") (pintype "input"))
    )
    (net (code "102") (name "unconnected-(U1-AUX_DA-Pad21)") (class "Default")
      (node (ref "U1") (pin "21") (pinfunction "AUX_DA_21") (pintype "input"))
    )
    (net (code "103") (name "unconnected-(U1-INT-Pad12)") (class "Default")
      (node (ref "U1") (pin "12") (pinfunction "INT_12") (pintype "output"))
    )
    (net (code "104") (name "unconnected-(U1-RESV_1-Pad1)") (class "Default")
      (node (ref "U1") (pin "1") (pinfunction "RESV_1_1") (pintype "passive"))
    )
    (net (code "105") (name "unconnected-(U1-RESV_19-Pad19)") (class "Default")
      (node (ref "U1") (pin "19") (pinfunction "RESV_19_19") (pintype "passive"))
    )
    (net (code "106") (name "unconnected-(U3-RESET-Pad7)") (class "Default")
      (node (ref "U3") (pin "7") (pinfunction "RESET_7") (pintype "bidirectional"))
    )
    (net (code "107") (name "unconnected-(U3-WP-Pad3)") (class "Default")
      (node (ref "U3") (pin "3") (pinfunction "WP_3") (pintype "bidirectional"))
    )
    (net (code "108") (name "unconnected-(U4-GPIO_7{slash}BOOT-Pad7)") (class "Default")
      (node (ref "U4") (pin "7") (pinfunction "GPIO_7/BOOT_7") (pintype "bidirectional"))
    )
    (net (code "109") (name "unconnected-(U4-GPIO_16-Pad16)") (class "Default")
      (node (ref "U4") (pin "16") (pinfunction "GPIO_16_16") (pintype "bidirectional"))
    )
    (net (code "110") (name "unconnected-(U4-GPIO_17-Pad17)") (class "Default")
      (node (ref "U4") (pin "17") (pinfunction "GPIO_17_17") (pintype "bidirectional"))
    )
    (net (code "111") (name "unconnected-(U4-GPIO_18-Pad18)") (class "Default")
      (node (ref "U4") (pin "18") (pinfunction "GPIO_18_18") (pintype "bidirectional"))
    )
    (net (code "112") (name "unconnected-(U4-GPIO_27-Pad27)") (class "Default")
      (node (ref "U4") (pin "27") (pinfunction "GPIO_27_27") (pintype "bidirectional"))
    )
    (net (code "113") (name "unconnected-(U4-GPIO_28{slash}NFC1-Pad28)") (class "Default")
      (node (ref "U4") (pin "28") (pinfunction "GPIO_28/NFC1_28") (pintype "bidirectional"))
    )
    (net (code "114") (name "unconnected-(U4-GPIO_29{slash}NFC2-Pad29)") (class "Default")
      (node (ref "U4") (pin "29") (pinfunction "GPIO_29/NFC2_29") (pintype "bidirectional"))
    )
    (net (code "115") (name "unconnected-(U4-I2C_SCL-Pad25)") (class "Default")
      (node (ref "U4") (pin "25") (pinfunction "I2C_SCL_25") (pintype "bidirectional"))
    )
    (net (code "116") (name "unconnected-(U4-I2C_SDA-Pad24)") (class "Default")
      (node (ref "U4") (pin "24") (pinfunction "I2C_SDA_24") (pintype "bidirectional"))
    )
    (net (code "117") (name "unconnected-(U4-NC-Pad13)") (class "Default")
      (node (ref "U4") (pin "13") (pinfunction "NC_13") (pintype "no_connect"))
    )
    (net (code "118") (name "unconnected-(U4-SPI0_CLK-Pad5)") (class "Default")
      (node (ref "U4") (pin "5") (pinfunction "SPI0_CLK_5") (pintype "bidirectional"))
    )
    (net (code "119") (name "unconnected-(U4-SPI0_MISO-Pad3)") (class "Default")
      (node (ref "U4") (pin "3") (pinfunction "SPI0_MISO_3") (pintype "bidirectional"))
    )
    (net (code "120") (name "unconnected-(U4-SPI0_MOSI-Pad4)") (class "Default")
      (node (ref "U4") (pin "4") (pinfunction "SPI0_MOSI_4") (pintype "bidirectional"))
    )
    (net (code "121") (name "unconnected-(U4-SWDCLK-Pad11)") (class "Default")
      (node (ref "U4") (pin "11") (pinfunction "SWDCLK_11") (pintype "input"))
    )
    (net (code "122") (name "unconnected-(U4-SWDIO-Pad15)") (class "Default")
      (node (ref "U4") (pin "15") (pinfunction "SWDIO_15") (pintype "bidirectional"))
    )
    (net (code "123") (name "unconnected-(U4-SWO-Pad8)") (class "Default")
      (node (ref "U4") (pin "8") (pinfunction "SWO_8") (pintype "output"))
    )
    (net (code "124") (name "unconnected-(U4-UART_CTS-Pad21)") (class "Default")
      (node (ref "U4") (pin "21") (pinfunction "UART_CTS_21") (pintype "bidirectional"))
    )
    (net (code "125") (name "unconnected-(U4-UART_RTS-Pad20)") (class "Default")
      (node (ref "U4") (pin "20") (pinfunction "UART_RTS_20") (pintype "bidirectional"))
    )
    (net (code "126") (name "unconnected-(U4-~{RESET}-Pad19)") (class "Default")
      (node (ref "U4") (pin "19") (pinfunction "~{RESET}_19") (pintype "input"))
    )
    (net (code "127") (name "unconnected-(U4-~{SPI0_CS0}-Pad2)") (class "Default")
      (node (ref "U4") (pin "2") (pinfunction "~{SPI0_CS0}_2") (pintype "bidirectional"))
    )
    (net (code "128") (name "unconnected-(U4-~{SPI0_CS1}-Pad1)") (class "Default")
      (node (ref "U4") (pin "1") (pinfunction "~{SPI0_CS1}_1") (pintype "output"))
    )
  )
)
